# MySensors_AirQuality_Board_2017-11-14_Au.net
KiCad netlist of a schematic drawn in EAGLE
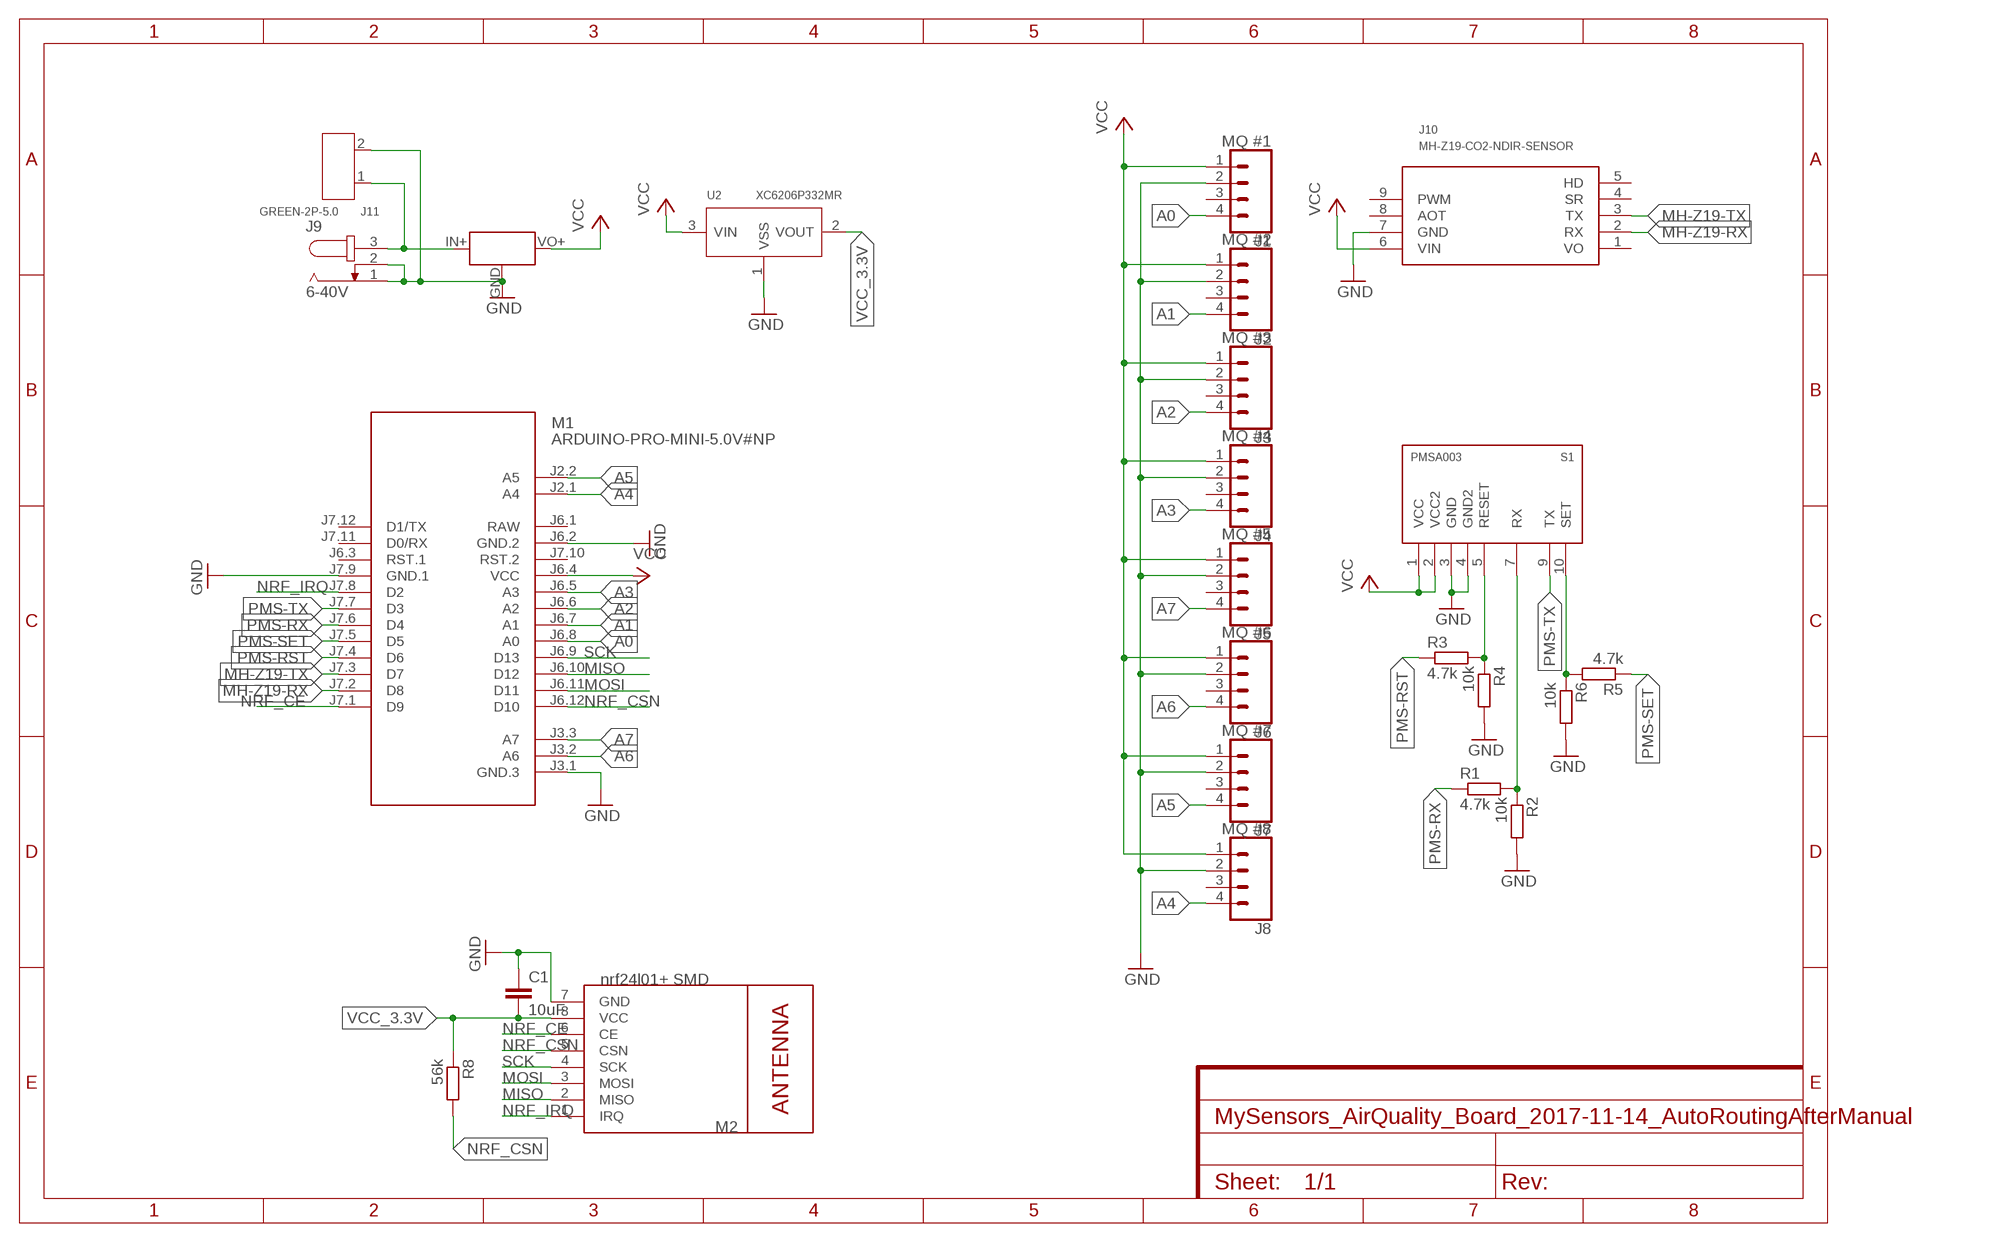
[diagram p0: schematic, sheet 1]

(export (version "E")
  (design (tool "Eeschema 10.0.6"))
  (components
    (comp (ref "C1")
      (value "10uF")
      (footprint "eagle-import:C0805")
      (libsource (lib "eagle-import") (part "C-EUC0805"))
    )
    (comp (ref "J1")
      (value "MQ #1")
      (footprint "eagle-import:1X04")
      (libsource (lib "eagle-import") (part "CONN_04"))
    )
    (comp (ref "J2")
      (value "MQ #2")
      (footprint "eagle-import:1X04")
      (libsource (lib "eagle-import") (part "CONN_04"))
    )
    (comp (ref "J3")
      (value "MQ #3")
      (footprint "eagle-import:1X04")
      (libsource (lib "eagle-import") (part "CONN_04"))
    )
    (comp (ref "J4")
      (value "MQ #4")
      (footprint "eagle-import:1X04")
      (libsource (lib "eagle-import") (part "CONN_04"))
    )
    (comp (ref "J5")
      (value "MQ #5")
      (footprint "eagle-import:1X04")
      (libsource (lib "eagle-import") (part "CONN_04"))
    )
    (comp (ref "J6")
      (value "MQ #6")
      (footprint "eagle-import:1X04")
      (libsource (lib "eagle-import") (part "CONN_04"))
    )
    (comp (ref "J7")
      (value "MQ #7")
      (footprint "eagle-import:1X04")
      (libsource (lib "eagle-import") (part "CONN_04"))
    )
    (comp (ref "J8")
      (value "MQ #8")
      (footprint "eagle-import:1X04")
      (libsource (lib "eagle-import") (part "CONN_04"))
    )
    (comp (ref "J9")
      (value "6-40V")
      (footprint "eagle-import:SPC4078")
      (libsource (lib "eagle-import") (part "JACK-PLUG1"))
    )
    (comp (ref "J10")
      (value "MH-Z19-CO2-NDIR-SENSOR")
      (footprint "eagle-import:MH-Z19")
      (libsource (lib "eagle-import") (part "MH-Z19-CO2-NDIR-SENSOR"))
    )
    (comp (ref "J11")
      (value "GREEN-2P-5.0")
      (footprint "eagle-import:H2-5.0-10.5X8.0MM")
      (libsource (lib "eagle-import") (part "SCREW-TERMINAL-GREEN(2P-5.0)"))
    )
    (comp (ref "M1")
      (value "ARDUINO-PRO-MINI-5.0V#NP")
      (footprint "eagle-import:ARDUINO-PRO-MINI#NP")
      (libsource (lib "eagle-import") (part "ARDUINO-PRO-MINI-#NP5.0V"))
    )
    (comp (ref "M2")
      (value "nrf24l01+ SMD")
      (footprint "eagle-import:WIRELESS-NRF24L01-SMD")
      (libsource (lib "eagle-import") (part "WIRELESS-NRF24L01SMD"))
    )
    (comp (ref "R1")
      (value "4.7k")
      (footprint "eagle-import:R0805")
      (libsource (lib "eagle-import") (part "resistor_348_R-EU_R0805"))
    )
    (comp (ref "R2")
      (value "10k")
      (footprint "eagle-import:R0805")
      (libsource (lib "eagle-import") (part "resistor_348_R-EU_R0805"))
    )
    (comp (ref "R3")
      (value "4.7k")
      (footprint "eagle-import:R0805")
      (libsource (lib "eagle-import") (part "resistor_348_R-EU_R0805"))
    )
    (comp (ref "R4")
      (value "10k")
      (footprint "eagle-import:R0805")
      (libsource (lib "eagle-import") (part "resistor_348_R-EU_R0805"))
    )
    (comp (ref "R5")
      (value "4.7k")
      (footprint "eagle-import:R0805")
      (libsource (lib "eagle-import") (part "resistor_348_R-EU_R0805"))
    )
    (comp (ref "R6")
      (value "10k")
      (footprint "eagle-import:R0805")
      (libsource (lib "eagle-import") (part "resistor_348_R-EU_R0805"))
    )
    (comp (ref "R8")
      (value "56k")
      (footprint "eagle-import:R0805")
      (libsource (lib "eagle-import") (part "R-EU_R0805"))
    )
    (comp (ref "S1")
      (value "PMSA003")
      (footprint "eagle-import:PMSA003")
      (libsource (lib "eagle-import") (part "PMSA003"))
    )
    (comp (ref "U$2")
      (value "MINI_BUCK_CONVERTER")
      (footprint "eagle-import:MINI_BUCK_CONVERTER")
      (libsource (lib "eagle-import") (part "MINI_BUCK_CONVERTER"))
    )
    (comp (ref "U2")
      (value "XC6206P332MR")
      (footprint "eagle-import:SOT-23")
      (fields (field (name "MPN") "XC6206P332MR-G"))
      (libsource (lib "eagle-import") (part "PMIC-LDO-XC6206P332MR-G(SOT23)"))
    )
  )
  (nets
    (net (code "1") (name "/MISO") (class "Default")
      (node (ref "M1") (pin "J6.10") (pinfunction "D12_J6.10") (pintype "bidirectional"))
      (node (ref "M2") (pin "2") (pinfunction "MISO_2") (pintype "bidirectional"))
    )
    (net (code "2") (name "/MOSI") (class "Default")
      (node (ref "M1") (pin "J6.11") (pinfunction "D11_J6.11") (pintype "bidirectional"))
      (node (ref "M2") (pin "3") (pinfunction "MOSI_3") (pintype "bidirectional"))
    )
    (net (code "3") (name "/NRF_CE") (class "Default")
      (node (ref "M1") (pin "J7.1") (pinfunction "D9_J7.1") (pintype "bidirectional"))
      (node (ref "M2") (pin "6") (pinfunction "CE_6") (pintype "bidirectional"))
    )
    (net (code "4") (name "/NRF_IRQ") (class "Default")
      (node (ref "M1") (pin "J7.8") (pinfunction "D2_J7.8") (pintype "bidirectional"))
      (node (ref "M2") (pin "1") (pinfunction "IRQ_1") (pintype "bidirectional"))
    )
    (net (code "5") (name "/RAW") (class "Default")
      (node (ref "M1") (pin "J6.1") (pinfunction "RAW_J6.1") (pintype "power_in"))
    )
    (net (code "6") (name "/SCK") (class "Default")
      (node (ref "M1") (pin "J6.9") (pinfunction "D13_J6.9") (pintype "bidirectional"))
      (node (ref "M2") (pin "4") (pinfunction "SCK_4") (pintype "bidirectional"))
    )
    (net (code "7") (name "/VO") (class "Default")
      (node (ref "J10") (pin "1") (pinfunction "VO_1") (pintype "power_in"))
    )
    (net (code "8") (name "A0") (class "Default")
      (node (ref "J1") (pin "4") (pinfunction "4_4") (pintype "passive"))
      (node (ref "M1") (pin "J6.8") (pinfunction "A0_J6.8") (pintype "bidirectional"))
    )
    (net (code "9") (name "A1") (class "Default")
      (node (ref "J2") (pin "4") (pinfunction "4_4") (pintype "passive"))
      (node (ref "M1") (pin "J6.7") (pinfunction "A1_J6.7") (pintype "bidirectional"))
    )
    (net (code "10") (name "A2") (class "Default")
      (node (ref "J3") (pin "4") (pinfunction "4_4") (pintype "passive"))
      (node (ref "M1") (pin "J6.6") (pinfunction "A2_J6.6") (pintype "bidirectional"))
    )
    (net (code "11") (name "A3") (class "Default")
      (node (ref "J4") (pin "4") (pinfunction "4_4") (pintype "passive"))
      (node (ref "M1") (pin "J6.5") (pinfunction "A3_J6.5") (pintype "bidirectional"))
    )
    (net (code "12") (name "A4") (class "Default")
      (node (ref "J8") (pin "4") (pinfunction "4_4") (pintype "passive"))
      (node (ref "M1") (pin "J2.1") (pinfunction "A4_J2.1") (pintype "bidirectional"))
    )
    (net (code "13") (name "A5") (class "Default")
      (node (ref "J7") (pin "4") (pinfunction "4_4") (pintype "passive"))
      (node (ref "M1") (pin "J2.2") (pinfunction "A5_J2.2") (pintype "bidirectional"))
    )
    (net (code "14") (name "A6") (class "Default")
      (node (ref "J6") (pin "4") (pinfunction "4_4") (pintype "passive"))
      (node (ref "M1") (pin "J3.2") (pinfunction "A6_J3.2") (pintype "bidirectional"))
    )
    (net (code "15") (name "A7") (class "Default")
      (node (ref "J5") (pin "4") (pinfunction "4_4") (pintype "passive"))
      (node (ref "M1") (pin "J3.3") (pinfunction "A7_J3.3") (pintype "bidirectional"))
    )
    (net (code "16") (name "GND") (class "Default")
      (node (ref "C1") (pin "1") (pinfunction "1_1") (pintype "passive"))
      (node (ref "J1") (pin "2") (pinfunction "2_2") (pintype "passive"))
      (node (ref "J10") (pin "7") (pinfunction "GND_7") (pintype "power_in"))
      (node (ref "J11") (pin "2") (pinfunction "2_2") (pintype "bidirectional"))
      (node (ref "J2") (pin "2") (pinfunction "2_2") (pintype "passive"))
      (node (ref "J3") (pin "2") (pinfunction "2_2") (pintype "passive"))
      (node (ref "J4") (pin "2") (pinfunction "2_2") (pintype "passive"))
      (node (ref "J5") (pin "2") (pinfunction "2_2") (pintype "passive"))
      (node (ref "J6") (pin "2") (pinfunction "2_2") (pintype "passive"))
      (node (ref "J7") (pin "2") (pinfunction "2_2") (pintype "passive"))
      (node (ref "J8") (pin "2") (pinfunction "2_2") (pintype "passive"))
      (node (ref "J9") (pin "1") (pinfunction "1_1") (pintype "passive"))
      (node (ref "J9") (pin "2") (pinfunction "2_2") (pintype "passive"))
      (node (ref "M1") (pin "J3.1") (pinfunction "GND.3_J3.1") (pintype "bidirectional"))
      (node (ref "M1") (pin "J6.2") (pinfunction "GND.2_J6.2") (pintype "power_in"))
      (node (ref "M1") (pin "J7.9") (pinfunction "GND.1_J7.9") (pintype "power_in"))
      (node (ref "M2") (pin "7") (pinfunction "GND_7") (pintype "power_in"))
      (node (ref "R2") (pin "2") (pinfunction "2_2") (pintype "passive"))
      (node (ref "R4") (pin "2") (pinfunction "2_2") (pintype "passive"))
      (node (ref "R6") (pin "2") (pinfunction "2_2") (pintype "passive"))
      (node (ref "S1") (pin "3") (pinfunction "GND_3") (pintype "bidirectional"))
      (node (ref "S1") (pin "4") (pinfunction "GND2_4") (pintype "bidirectional"))
      (node (ref "U$2") (pin "GND") (pinfunction "GND_GND") (pintype "bidirectional"))
      (node (ref "U2") (pin "1") (pinfunction "VSS_1") (pintype "power_in"))
    )
    (net (code "17") (name "MH-Z19-RX") (class "Default")
      (node (ref "J10") (pin "2") (pinfunction "RX_2") (pintype "input"))
      (node (ref "M1") (pin "J7.2") (pinfunction "D8_J7.2") (pintype "bidirectional"))
    )
    (net (code "18") (name "MH-Z19-TX") (class "Default")
      (node (ref "J10") (pin "3") (pinfunction "TX_3") (pintype "output"))
      (node (ref "M1") (pin "J7.3") (pinfunction "D7_J7.3") (pintype "bidirectional"))
    )
    (net (code "19") (name "NRF_CSN") (class "Default")
      (node (ref "M1") (pin "J6.12") (pinfunction "D10_J6.12") (pintype "bidirectional"))
      (node (ref "M2") (pin "5") (pinfunction "CSN_5") (pintype "bidirectional"))
      (node (ref "R8") (pin "2") (pinfunction "2_2") (pintype "passive"))
    )
    (net (code "20") (name "Net-(S1-RESET)") (class "Default")
      (node (ref "R3") (pin "2") (pinfunction "2_2") (pintype "passive"))
      (node (ref "R4") (pin "1") (pinfunction "1_1") (pintype "passive"))
      (node (ref "S1") (pin "5") (pinfunction "RESET_5") (pintype "bidirectional"))
    )
    (net (code "21") (name "Net-(S1-RX)") (class "Default")
      (node (ref "R1") (pin "2") (pinfunction "2_2") (pintype "passive"))
      (node (ref "R2") (pin "1") (pinfunction "1_1") (pintype "passive"))
      (node (ref "S1") (pin "7") (pinfunction "RX_7") (pintype "bidirectional"))
    )
    (net (code "22") (name "Net-(S1-SET)") (class "Default")
      (node (ref "R5") (pin "2") (pinfunction "2_2") (pintype "passive"))
      (node (ref "R6") (pin "1") (pinfunction "1_1") (pintype "passive"))
      (node (ref "S1") (pin "10") (pinfunction "SET_10") (pintype "bidirectional"))
    )
    (net (code "23") (name "Net-(U$2-VIN)") (class "Default")
      (node (ref "J11") (pin "1") (pinfunction "1_1") (pintype "bidirectional"))
      (node (ref "J9") (pin "3") (pinfunction "3_3") (pintype "passive"))
      (node (ref "U$2") (pin "IN+") (pinfunction "VIN_IN+") (pintype "input"))
    )
    (net (code "24") (name "PMS-RST") (class "Default")
      (node (ref "M1") (pin "J7.4") (pinfunction "D6_J7.4") (pintype "bidirectional"))
      (node (ref "R3") (pin "1") (pinfunction "1_1") (pintype "passive"))
    )
    (net (code "25") (name "PMS-RX") (class "Default")
      (node (ref "M1") (pin "J7.6") (pinfunction "D4_J7.6") (pintype "bidirectional"))
      (node (ref "R1") (pin "1") (pinfunction "1_1") (pintype "passive"))
    )
    (net (code "26") (name "PMS-SET") (class "Default")
      (node (ref "M1") (pin "J7.5") (pinfunction "D5_J7.5") (pintype "bidirectional"))
      (node (ref "R5") (pin "1") (pinfunction "1_1") (pintype "passive"))
    )
    (net (code "27") (name "PMS-TX") (class "Default")
      (node (ref "M1") (pin "J7.7") (pinfunction "D3_J7.7") (pintype "bidirectional"))
      (node (ref "S1") (pin "9") (pinfunction "TX_9") (pintype "bidirectional"))
    )
    (net (code "28") (name "VCC") (class "Default")
      (node (ref "J1") (pin "1") (pinfunction "1_1") (pintype "passive"))
      (node (ref "J10") (pin "6") (pinfunction "VIN_6") (pintype "power_in"))
      (node (ref "J2") (pin "1") (pinfunction "1_1") (pintype "passive"))
      (node (ref "J3") (pin "1") (pinfunction "1_1") (pintype "passive"))
      (node (ref "J4") (pin "1") (pinfunction "1_1") (pintype "passive"))
      (node (ref "J5") (pin "1") (pinfunction "1_1") (pintype "passive"))
      (node (ref "J6") (pin "1") (pinfunction "1_1") (pintype "passive"))
      (node (ref "J7") (pin "1") (pinfunction "1_1") (pintype "passive"))
      (node (ref "J8") (pin "1") (pinfunction "1_1") (pintype "passive"))
      (node (ref "M1") (pin "J6.4") (pinfunction "VCC_J6.4") (pintype "power_in"))
      (node (ref "S1") (pin "1") (pinfunction "VCC_1") (pintype "bidirectional"))
      (node (ref "S1") (pin "2") (pinfunction "VCC2_2") (pintype "bidirectional"))
      (node (ref "U$2") (pin "VO+") (pinfunction "VOUT_VO+") (pintype "power_in"))
      (node (ref "U2") (pin "3") (pinfunction "VIN_3") (pintype "input"))
    )
    (net (code "29") (name "VCC_3.3V") (class "Default")
      (node (ref "C1") (pin "2") (pinfunction "2_2") (pintype "passive"))
      (node (ref "M2") (pin "8") (pinfunction "VCC_8") (pintype "power_in"))
      (node (ref "R8") (pin "1") (pinfunction "1_1") (pintype "passive"))
      (node (ref "U2") (pin "2") (pinfunction "VOUT_2") (pintype "output"))
    )
    (net (code "30") (name "unconnected-(J1-Pad3)") (class "Default")
      (node (ref "J1") (pin "3") (pinfunction "3_3") (pintype "passive"))
    )
    (net (code "31") (name "unconnected-(J2-Pad3)") (class "Default")
      (node (ref "J2") (pin "3") (pinfunction "3_3") (pintype "passive"))
    )
    (net (code "32") (name "unconnected-(J3-Pad3)") (class "Default")
      (node (ref "J3") (pin "3") (pinfunction "3_3") (pintype "passive"))
    )
    (net (code "33") (name "unconnected-(J4-Pad3)") (class "Default")
      (node (ref "J4") (pin "3") (pinfunction "3_3") (pintype "passive"))
    )
    (net (code "34") (name "unconnected-(J5-Pad3)") (class "Default")
      (node (ref "J5") (pin "3") (pinfunction "3_3") (pintype "passive"))
    )
    (net (code "35") (name "unconnected-(J6-Pad3)") (class "Default")
      (node (ref "J6") (pin "3") (pinfunction "3_3") (pintype "passive"))
    )
    (net (code "36") (name "unconnected-(J7-Pad3)") (class "Default")
      (node (ref "J7") (pin "3") (pinfunction "3_3") (pintype "passive"))
    )
    (net (code "37") (name "unconnected-(J8-Pad3)") (class "Default")
      (node (ref "J8") (pin "3") (pinfunction "3_3") (pintype "passive"))
    )
    (net (code "38") (name "unconnected-(J10-AOT-Pad8)") (class "Default")
      (node (ref "J10") (pin "8") (pinfunction "AOT_8") (pintype "no_connect"))
    )
    (net (code "39") (name "unconnected-(J10-HD-Pad5)") (class "Default")
      (node (ref "J10") (pin "5") (pinfunction "HD_5") (pintype "input"))
    )
    (net (code "40") (name "unconnected-(J10-PWM-Pad9)") (class "Default")
      (node (ref "J10") (pin "9") (pinfunction "PWM_9") (pintype "output"))
    )
    (net (code "41") (name "unconnected-(J10-SR-Pad4)") (class "Default")
      (node (ref "J10") (pin "4") (pinfunction "SR_4") (pintype "no_connect"))
    )
    (net (code "42") (name "unconnected-(M1-D0{slash}RX-PadJ7.11)") (class "Default")
      (node (ref "M1") (pin "J7.11") (pinfunction "D0/RX_J7.11") (pintype "bidirectional"))
    )
    (net (code "43") (name "unconnected-(M1-D1{slash}TX-PadJ7.12)") (class "Default")
      (node (ref "M1") (pin "J7.12") (pinfunction "D1/TX_J7.12") (pintype "bidirectional"))
    )
    (net (code "44") (name "unconnected-(M1-RST.1-PadJ6.3)") (class "Default")
      (node (ref "M1") (pin "J6.3") (pinfunction "RST.1_J6.3") (pintype "bidirectional"))
    )
    (net (code "45") (name "unconnected-(M1-RST.2-PadJ7.10)") (class "Default")
      (node (ref "M1") (pin "J7.10") (pinfunction "RST.2_J7.10") (pintype "bidirectional"))
    )
  )
)
